# soundmotorboard.net
KiCad netlist of a schematic drawn in EAGLE
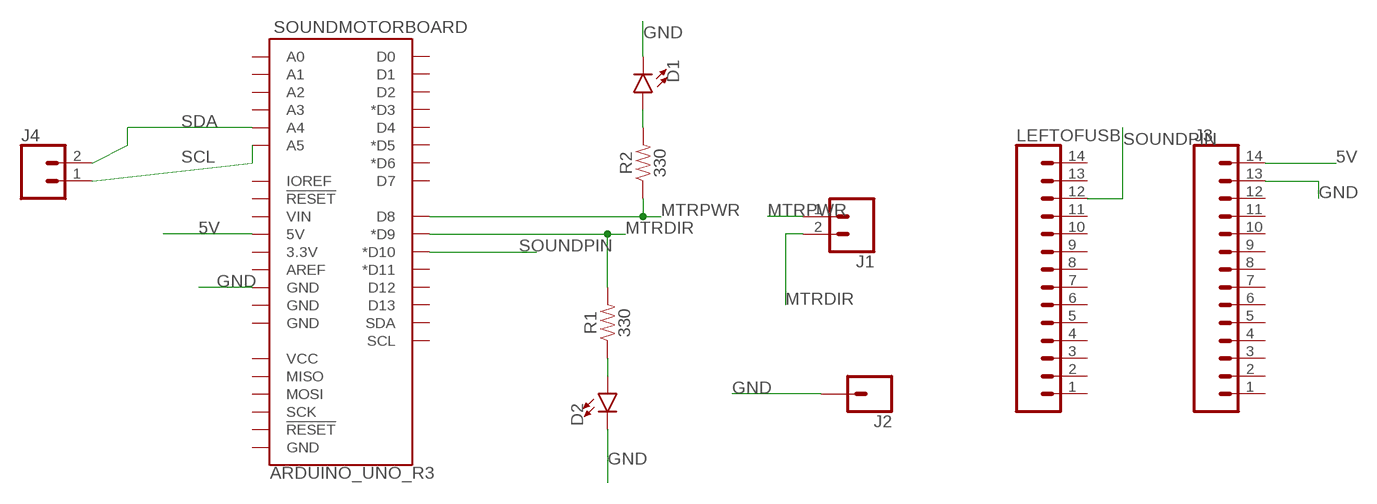
[diagram p0: schematic, sheet 1]

(export (version "E")
  (design (tool "Eeschema 10.0.6"))
  (components
    (comp (ref "D1")
      (value "LED5MM")
      (footprint "eagle-import:LED_5MM")
      (libsource (lib "eagle-import") (part "LED5MM"))
    )
    (comp (ref "D2")
      (value "LED5MM")
      (footprint "eagle-import:LED_5MM")
      (libsource (lib "eagle-import") (part "LED5MM"))
    )
    (comp (ref "J1")
      (value "CONN_023.5MM-NO_SILK")
      (footprint "eagle-import:SCREWTERMINAL-3.5MM-2-NS")
      (libsource (lib "eagle-import") (part "CONN_023.5MM-NO_SILK"))
    )
    (comp (ref "J2")
      (value "CONN_01")
      (footprint "eagle-import:1X01")
      (libsource (lib "eagle-import") (part "CONN_01"))
    )
    (comp (ref "J3")
      (value "CONN_14")
      (footprint "eagle-import:1X14")
      (libsource (lib "eagle-import") (part "CONN_14"))
    )
    (comp (ref "J4")
      (value "CONN_023.5MM")
      (footprint "eagle-import:SCREWTERMINAL-3.5MM-2")
      (libsource (lib "eagle-import") (part "CONN_023.5MM"))
    )
    (comp (ref "LEFTOFUSB")
      (value "CONN_14")
      (footprint "eagle-import:1X14")
      (libsource (lib "eagle-import") (part "CONN_14"))
    )
    (comp (ref "R1")
      (value "330")
      (footprint "eagle-import:AXIAL-0.3")
      (libsource (lib "eagle-import") (part "330OHM-HORIZ-1/10W-5%"))
    )
    (comp (ref "R2")
      (value "330")
      (footprint "eagle-import:AXIAL-0.3")
      (libsource (lib "eagle-import") (part "330OHM-HORIZ-1/10W-5%"))
    )
    (comp (ref "SOUNDMOTORBOARD")
      (value "ARDUINO_UNO_R3")
      (footprint "eagle-import:ARDUINO_R3")
      (libsource (lib "eagle-import") (part "ARDUINO_UNO_R3"))
    )
  )
  (nets
    (net (code "1") (name "/5V") (class "Default")
      (node (ref "J3") (pin "14") (pinfunction "14_14") (pintype "passive"))
      (node (ref "SOUNDMOTORBOARD") (pin "5V") (pinfunction "5V_5V") (pintype "bidirectional"))
    )
    (net (code "2") (name "/GND") (class "Default")
      (node (ref "D1") (pin "K") (pinfunction "C_K") (pintype "passive"))
      (node (ref "D2") (pin "K") (pinfunction "C_K") (pintype "passive"))
      (node (ref "J2") (pin "1") (pinfunction "1_1") (pintype "passive"))
      (node (ref "J3") (pin "13") (pinfunction "13_13") (pintype "passive"))
      (node (ref "SOUNDMOTORBOARD") (pin "GND@4") (pinfunction "GND_GND@4") (pintype "bidirectional"))
    )
    (net (code "3") (name "/MTRDIR") (class "Default")
      (node (ref "J1") (pin "2") (pinfunction "2_2") (pintype "passive"))
      (node (ref "R1") (pin "P$2") (pinfunction "2_P$2") (pintype "passive"))
      (node (ref "SOUNDMOTORBOARD") (pin "D9") (pinfunction "*D9_D9") (pintype "bidirectional"))
    )
    (net (code "4") (name "/MTRPWR") (class "Default")
      (node (ref "J1") (pin "1") (pinfunction "1_1") (pintype "passive"))
      (node (ref "R2") (pin "P$1") (pinfunction "1_P$1") (pintype "passive"))
      (node (ref "SOUNDMOTORBOARD") (pin "D8") (pinfunction "D8_D8") (pintype "bidirectional"))
    )
    (net (code "5") (name "/SCL") (class "Default")
      (node (ref "J4") (pin "1") (pinfunction "1_1") (pintype "passive"))
      (node (ref "SOUNDMOTORBOARD") (pin "A5") (pinfunction "A5_A5") (pintype "bidirectional"))
    )
    (net (code "6") (name "/SDA") (class "Default")
      (node (ref "J4") (pin "2") (pinfunction "2_2") (pintype "passive"))
      (node (ref "SOUNDMOTORBOARD") (pin "A4") (pinfunction "A4_A4") (pintype "bidirectional"))
    )
    (net (code "7") (name "/SOUNDPIN") (class "Default")
      (node (ref "LEFTOFUSB") (pin "12") (pinfunction "12_12") (pintype "passive"))
      (node (ref "SOUNDMOTORBOARD") (pin "D10") (pinfunction "*D10_D10") (pintype "bidirectional"))
    )
    (net (code "8") (name "Net-(R1-1)") (class "Default")
      (node (ref "D2") (pin "A") (pinfunction "A_A") (pintype "passive"))
      (node (ref "R1") (pin "P$1") (pinfunction "1_P$1") (pintype "passive"))
    )
    (net (code "9") (name "Net-(R2-2)") (class "Default")
      (node (ref "D1") (pin "A") (pinfunction "A_A") (pintype "passive"))
      (node (ref "R2") (pin "P$2") (pinfunction "2_P$2") (pintype "passive"))
    )
    (net (code "10") (name "unconnected-(J3-Pad1)") (class "Default")
      (node (ref "J3") (pin "1") (pinfunction "1_1") (pintype "passive"))
    )
    (net (code "11") (name "unconnected-(J3-Pad2)") (class "Default")
      (node (ref "J3") (pin "2") (pinfunction "2_2") (pintype "passive"))
    )
    (net (code "12") (name "unconnected-(J3-Pad3)") (class "Default")
      (node (ref "J3") (pin "3") (pinfunction "3_3") (pintype "passive"))
    )
    (net (code "13") (name "unconnected-(J3-Pad4)") (class "Default")
      (node (ref "J3") (pin "4") (pinfunction "4_4") (pintype "passive"))
    )
    (net (code "14") (name "unconnected-(J3-Pad5)") (class "Default")
      (node (ref "J3") (pin "5") (pinfunction "5_5") (pintype "passive"))
    )
    (net (code "15") (name "unconnected-(J3-Pad6)") (class "Default")
      (node (ref "J3") (pin "6") (pinfunction "6_6") (pintype "passive"))
    )
    (net (code "16") (name "unconnected-(J3-Pad7)") (class "Default")
      (node (ref "J3") (pin "7") (pinfunction "7_7") (pintype "passive"))
    )
    (net (code "17") (name "unconnected-(J3-Pad8)") (class "Default")
      (node (ref "J3") (pin "8") (pinfunction "8_8") (pintype "passive"))
    )
    (net (code "18") (name "unconnected-(J3-Pad9)") (class "Default")
      (node (ref "J3") (pin "9") (pinfunction "9_9") (pintype "passive"))
    )
    (net (code "19") (name "unconnected-(J3-Pad10)") (class "Default")
      (node (ref "J3") (pin "10") (pinfunction "10_10") (pintype "passive"))
    )
    (net (code "20") (name "unconnected-(J3-Pad11)") (class "Default")
      (node (ref "J3") (pin "11") (pinfunction "11_11") (pintype "passive"))
    )
    (net (code "21") (name "unconnected-(J3-Pad12)") (class "Default")
      (node (ref "J3") (pin "12") (pinfunction "12_12") (pintype "passive"))
    )
    (net (code "22") (name "unconnected-(LEFTOFUSB-Pad1)") (class "Default")
      (node (ref "LEFTOFUSB") (pin "1") (pinfunction "1_1") (pintype "passive"))
    )
    (net (code "23") (name "unconnected-(LEFTOFUSB-Pad2)") (class "Default")
      (node (ref "LEFTOFUSB") (pin "2") (pinfunction "2_2") (pintype "passive"))
    )
    (net (code "24") (name "unconnected-(LEFTOFUSB-Pad3)") (class "Default")
      (node (ref "LEFTOFUSB") (pin "3") (pinfunction "3_3") (pintype "passive"))
    )
    (net (code "25") (name "unconnected-(LEFTOFUSB-Pad4)") (class "Default")
      (node (ref "LEFTOFUSB") (pin "4") (pinfunction "4_4") (pintype "passive"))
    )
    (net (code "26") (name "unconnected-(LEFTOFUSB-Pad5)") (class "Default")
      (node (ref "LEFTOFUSB") (pin "5") (pinfunction "5_5") (pintype "passive"))
    )
    (net (code "27") (name "unconnected-(LEFTOFUSB-Pad6)") (class "Default")
      (node (ref "LEFTOFUSB") (pin "6") (pinfunction "6_6") (pintype "passive"))
    )
    (net (code "28") (name "unconnected-(LEFTOFUSB-Pad7)") (class "Default")
      (node (ref "LEFTOFUSB") (pin "7") (pinfunction "7_7") (pintype "passive"))
    )
    (net (code "29") (name "unconnected-(LEFTOFUSB-Pad8)") (class "Default")
      (node (ref "LEFTOFUSB") (pin "8") (pinfunction "8_8") (pintype "passive"))
    )
    (net (code "30") (name "unconnected-(LEFTOFUSB-Pad9)") (class "Default")
      (node (ref "LEFTOFUSB") (pin "9") (pinfunction "9_9") (pintype "passive"))
    )
    (net (code "31") (name "unconnected-(LEFTOFUSB-Pad10)") (class "Default")
      (node (ref "LEFTOFUSB") (pin "10") (pinfunction "10_10") (pintype "passive"))
    )
    (net (code "32") (name "unconnected-(LEFTOFUSB-Pad11)") (class "Default")
      (node (ref "LEFTOFUSB") (pin "11") (pinfunction "11_11") (pintype "passive"))
    )
    (net (code "33") (name "unconnected-(LEFTOFUSB-Pad13)") (class "Default")
      (node (ref "LEFTOFUSB") (pin "13") (pinfunction "13_13") (pintype "passive"))
    )
    (net (code "34") (name "unconnected-(LEFTOFUSB-Pad14)") (class "Default")
      (node (ref "LEFTOFUSB") (pin "14") (pinfunction "14_14") (pintype "passive"))
    )
    (net (code "35") (name "unconnected-(SOUNDMOTORBOARD-*D3-PadD3)") (class "Default")
      (node (ref "SOUNDMOTORBOARD") (pin "D3") (pinfunction "*D3_D3") (pintype "bidirectional"))
    )
    (net (code "36") (name "unconnected-(SOUNDMOTORBOARD-*D5-PadD5)") (class "Default")
      (node (ref "SOUNDMOTORBOARD") (pin "D5") (pinfunction "*D5_D5") (pintype "bidirectional"))
    )
    (net (code "37") (name "unconnected-(SOUNDMOTORBOARD-*D6-PadD6)") (class "Default")
      (node (ref "SOUNDMOTORBOARD") (pin "D6") (pinfunction "*D6_D6") (pintype "bidirectional"))
    )
    (net (code "38") (name "unconnected-(SOUNDMOTORBOARD-*D11-PadD11)") (class "Default")
      (node (ref "SOUNDMOTORBOARD") (pin "D11") (pinfunction "*D11_D11") (pintype "bidirectional"))
    )
    (net (code "39") (name "unconnected-(SOUNDMOTORBOARD-GND-PadGND@1)") (class "Default")
      (node (ref "SOUNDMOTORBOARD") (pin "GND@1") (pinfunction "GND_GND@1") (pintype "bidirectional"))
    )
    (net (code "40") (name "unconnected-(SOUNDMOTORBOARD-GND-PadGND@2)") (class "Default")
      (node (ref "SOUNDMOTORBOARD") (pin "GND@2") (pinfunction "GND_GND@2") (pintype "bidirectional"))
    )
    (net (code "41") (name "unconnected-(SOUNDMOTORBOARD-GND-PadGND@3)") (class "Default")
      (node (ref "SOUNDMOTORBOARD") (pin "GND@3") (pinfunction "GND_GND@3") (pintype "bidirectional"))
    )
    (net (code "42") (name "unconnected-(SOUNDMOTORBOARD-Pad3.3V)") (class "Default")
      (node (ref "SOUNDMOTORBOARD") (pin "3.3V") (pinfunction "3.3V_3.3V") (pintype "bidirectional"))
    )
    (net (code "43") (name "unconnected-(SOUNDMOTORBOARD-PadA0)") (class "Default")
      (node (ref "SOUNDMOTORBOARD") (pin "A0") (pinfunction "A0_A0") (pintype "bidirectional"))
    )
    (net (code "44") (name "unconnected-(SOUNDMOTORBOARD-PadA1)") (class "Default")
      (node (ref "SOUNDMOTORBOARD") (pin "A1") (pinfunction "A1_A1") (pintype "bidirectional"))
    )
    (net (code "45") (name "unconnected-(SOUNDMOTORBOARD-PadA2)") (class "Default")
      (node (ref "SOUNDMOTORBOARD") (pin "A2") (pinfunction "A2_A2") (pintype "bidirectional"))
    )
    (net (code "46") (name "unconnected-(SOUNDMOTORBOARD-PadA3)") (class "Default")
      (node (ref "SOUNDMOTORBOARD") (pin "A3") (pinfunction "A3_A3") (pintype "bidirectional"))
    )
    (net (code "47") (name "unconnected-(SOUNDMOTORBOARD-PadAREF)") (class "Default")
      (node (ref "SOUNDMOTORBOARD") (pin "AREF") (pinfunction "AREF_AREF") (pintype "bidirectional"))
    )
    (net (code "48") (name "unconnected-(SOUNDMOTORBOARD-PadD0)") (class "Default")
      (node (ref "SOUNDMOTORBOARD") (pin "D0") (pinfunction "D0_D0") (pintype "bidirectional"))
    )
    (net (code "49") (name "unconnected-(SOUNDMOTORBOARD-PadD1)") (class "Default")
      (node (ref "SOUNDMOTORBOARD") (pin "D1") (pinfunction "D1_D1") (pintype "bidirectional"))
    )
    (net (code "50") (name "unconnected-(SOUNDMOTORBOARD-PadD2)") (class "Default")
      (node (ref "SOUNDMOTORBOARD") (pin "D2") (pinfunction "D2_D2") (pintype "bidirectional"))
    )
    (net (code "51") (name "unconnected-(SOUNDMOTORBOARD-PadD4)") (class "Default")
      (node (ref "SOUNDMOTORBOARD") (pin "D4") (pinfunction "D4_D4") (pintype "bidirectional"))
    )
    (net (code "52") (name "unconnected-(SOUNDMOTORBOARD-PadD7)") (class "Default")
      (node (ref "SOUNDMOTORBOARD") (pin "D7") (pinfunction "D7_D7") (pintype "bidirectional"))
    )
    (net (code "53") (name "unconnected-(SOUNDMOTORBOARD-PadD12)") (class "Default")
      (node (ref "SOUNDMOTORBOARD") (pin "D12") (pinfunction "D12_D12") (pintype "bidirectional"))
    )
    (net (code "54") (name "unconnected-(SOUNDMOTORBOARD-PadD13)") (class "Default")
      (node (ref "SOUNDMOTORBOARD") (pin "D13") (pinfunction "D13_D13") (pintype "bidirectional"))
    )
    (net (code "55") (name "unconnected-(SOUNDMOTORBOARD-PadIOREF)") (class "Default")
      (node (ref "SOUNDMOTORBOARD") (pin "IOREF") (pinfunction "IOREF_IOREF") (pintype "bidirectional"))
    )
    (net (code "56") (name "unconnected-(SOUNDMOTORBOARD-PadMISO)") (class "Default")
      (node (ref "SOUNDMOTORBOARD") (pin "MISO") (pinfunction "MISO_MISO") (pintype "bidirectional"))
    )
    (net (code "57") (name "unconnected-(SOUNDMOTORBOARD-PadMOSI)") (class "Default")
      (node (ref "SOUNDMOTORBOARD") (pin "MOSI") (pinfunction "MOSI_MOSI") (pintype "bidirectional"))
    )
    (net (code "58") (name "unconnected-(SOUNDMOTORBOARD-PadSCK)") (class "Default")
      (node (ref "SOUNDMOTORBOARD") (pin "SCK") (pinfunction "SCK_SCK") (pintype "bidirectional"))
    )
    (net (code "59") (name "unconnected-(SOUNDMOTORBOARD-PadSCL)") (class "Default")
      (node (ref "SOUNDMOTORBOARD") (pin "SCL") (pinfunction "SCL_SCL") (pintype "bidirectional"))
    )
    (net (code "60") (name "unconnected-(SOUNDMOTORBOARD-PadSDA)") (class "Default")
      (node (ref "SOUNDMOTORBOARD") (pin "SDA") (pinfunction "SDA_SDA") (pintype "bidirectional"))
    )
    (net (code "61") (name "unconnected-(SOUNDMOTORBOARD-PadVCC)") (class "Default")
      (node (ref "SOUNDMOTORBOARD") (pin "VCC") (pinfunction "VCC_VCC") (pintype "bidirectional"))
    )
    (net (code "62") (name "unconnected-(SOUNDMOTORBOARD-PadVIN)") (class "Default")
      (node (ref "SOUNDMOTORBOARD") (pin "VIN") (pinfunction "VIN_VIN") (pintype "bidirectional"))
    )
    (net (code "63") (name "unconnected-(SOUNDMOTORBOARD-~{RESET}-PadRESET@1)") (class "Default")
      (node (ref "SOUNDMOTORBOARD") (pin "RESET@1") (pinfunction "~{RESET}_RESET@1") (pintype "bidirectional"))
    )
    (net (code "64") (name "unconnected-(SOUNDMOTORBOARD-~{RESET}-PadRESET@2)") (class "Default")
      (node (ref "SOUNDMOTORBOARD") (pin "RESET@2") (pinfunction "~{RESET}_RESET@2") (pintype "bidirectional"))
    )
  )
)
